# elektrosluch_mini_city.net
KiCad netlist of a schematic drawn in EAGLE
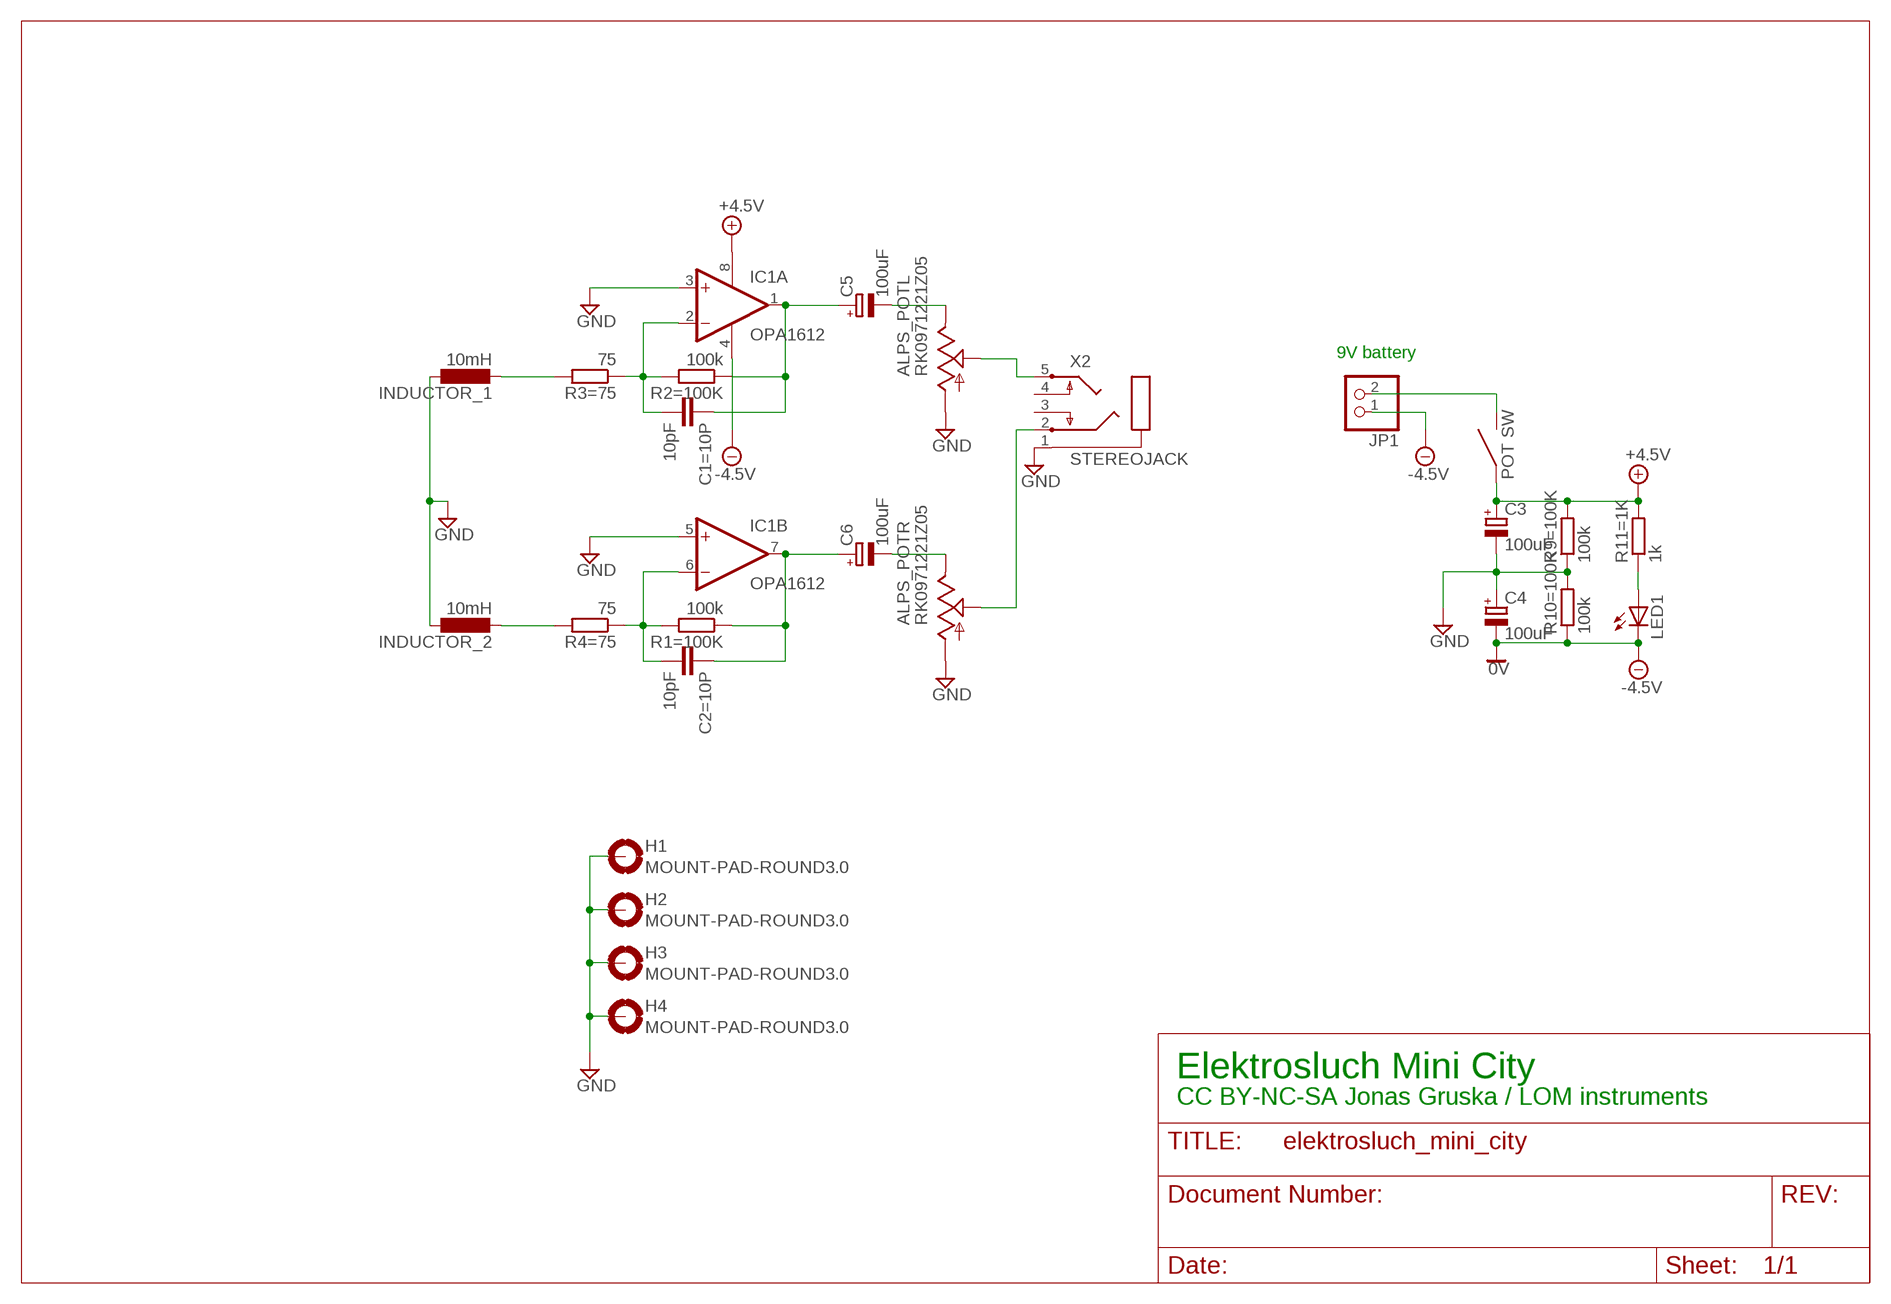
[diagram p0: schematic, sheet 1]

(export (version "E")
  (design (tool "Eeschema 10.0.6"))
  (components
    (comp (ref "ALPS_POT")
      (value "RK0971221Z05")
      (footprint "eagle-import:ALPS_RK0971221Z0X")
      (libsource (lib "eagle-import") (part "ALPS_RK0971221Z0N"))
    )
    (comp (ref "C1=10P")
      (value "10pF")
      (footprint "eagle-import:C050-024X044")
      (libsource (lib "eagle-import") (part "C-EU050-024X044"))
    )
    (comp (ref "C2=10P")
      (value "10pF")
      (footprint "eagle-import:C050-024X044")
      (libsource (lib "eagle-import") (part "C-EU050-024X044"))
    )
    (comp (ref "C3")
      (value "100uF")
      (footprint "eagle-import:E2,5-6")
      (libsource (lib "eagle-import") (part "CPOL-EUE2.5-6"))
    )
    (comp (ref "C4")
      (value "100uF")
      (footprint "eagle-import:E2,5-6")
      (libsource (lib "eagle-import") (part "CPOL-EUE2.5-6"))
    )
    (comp (ref "C5")
      (value "100uF")
      (footprint "eagle-import:E2,5-6")
      (libsource (lib "eagle-import") (part "CPOL-EUE2.5-6"))
    )
    (comp (ref "C6")
      (value "100uF")
      (footprint "eagle-import:E2,5-6")
      (libsource (lib "eagle-import") (part "CPOL-EUE2.5-6"))
    )
    (comp (ref "H1")
      (value "MOUNT-PAD-ROUND3.0")
      (footprint "eagle-import:3,0-PAD")
      (libsource (lib "eagle-import") (part "MOUNT-PAD-ROUND3.0"))
    )
    (comp (ref "H2")
      (value "MOUNT-PAD-ROUND3.0")
      (footprint "eagle-import:3,0-PAD")
      (libsource (lib "eagle-import") (part "MOUNT-PAD-ROUND3.0"))
    )
    (comp (ref "H3")
      (value "MOUNT-PAD-ROUND3.0")
      (footprint "eagle-import:3,0-PAD")
      (libsource (lib "eagle-import") (part "MOUNT-PAD-ROUND3.0"))
    )
    (comp (ref "H4")
      (value "MOUNT-PAD-ROUND3.0")
      (footprint "eagle-import:3,0-PAD")
      (libsource (lib "eagle-import") (part "MOUNT-PAD-ROUND3.0"))
    )
    (comp (ref "IC1")
      (value "OPA1612")
      (footprint "eagle-import:SO08")
      (libsource (lib "eagle-import") (part "OPA2UA134"))
    )
    (comp (ref "INDUCTOR_1")
      (value "10mH")
      (footprint "eagle-import:COIL")
      (libsource (lib "eagle-import") (part "COIL"))
    )
    (comp (ref "INDUCTOR_2")
      (value "10mH")
      (footprint "eagle-import:COIL")
      (libsource (lib "eagle-import") (part "COIL"))
    )
    (comp (ref "JP1")
      (value "PINHD-1X2")
      (footprint "eagle-import:1X02")
      (libsource (lib "eagle-import") (part "PINHD-1X2"))
    )
    (comp (ref "LED1")
      (value "LED3MM")
      (footprint "eagle-import:LED3MM")
      (libsource (lib "eagle-import") (part "LED3MM"))
    )
    (comp (ref "R1=100K")
      (value "100k")
      (footprint "eagle-import:0204_7")
      (libsource (lib "eagle-import") (part "R-EU_0204/7"))
    )
    (comp (ref "R2=100K")
      (value "100k")
      (footprint "eagle-import:0204_7")
      (libsource (lib "eagle-import") (part "R-EU_0204/7"))
    )
    (comp (ref "R3=75")
      (value "75")
      (footprint "eagle-import:0204_7")
      (libsource (lib "eagle-import") (part "R-EU_0204/7"))
    )
    (comp (ref "R4=75")
      (value "75")
      (footprint "eagle-import:0204_7")
      (libsource (lib "eagle-import") (part "R-EU_0204/7"))
    )
    (comp (ref "R9=100K")
      (value "100k")
      (footprint "eagle-import:0204_7")
      (libsource (lib "eagle-import") (part "R-EU_0204/7"))
    )
    (comp (ref "R10=100K")
      (value "100k")
      (footprint "eagle-import:0204_7")
      (libsource (lib "eagle-import") (part "R-EU_0204/7"))
    )
    (comp (ref "R11=1K")
      (value "1k")
      (footprint "eagle-import:0204_7")
      (libsource (lib "eagle-import") (part "R-EU_0204/7"))
    )
    (comp (ref "X2")
      (value "STEREOJACK")
      (footprint "eagle-import:STX3100")
      (libsource (lib "eagle-import") (part "STEREOJACK"))
    )
  )
  (nets
    (net (code "1") (name "+4.5V") (class "Default")
      (node (ref "ALPS_POT") (pin "S1") (pinfunction "S1_S1") (pintype "power_in"))
      (node (ref "C3") (pin "+") (pinfunction "+_+") (pintype "passive"))
      (node (ref "IC1") (pin "8") (pinfunction "V+_8") (pintype "power_in"))
      (node (ref "R11=1K") (pin "2") (pinfunction "2_2") (pintype "passive"))
      (node (ref "R9=100K") (pin "2") (pinfunction "2_2") (pintype "passive"))
    )
    (net (code "2") (name "-4.5V") (class "Default")
      (node (ref "C4") (pin "-") (pinfunction "-_-") (pintype "passive"))
      (node (ref "IC1") (pin "4") (pinfunction "V-_4") (pintype "power_in"))
      (node (ref "JP1") (pin "1") (pinfunction "1_1") (pintype "passive"))
      (node (ref "LED1") (pin "K") (pinfunction "C_K") (pintype "passive"))
      (node (ref "R10=100K") (pin "1") (pinfunction "1_1") (pintype "passive"))
    )
    (net (code "3") (name "GND") (class "Default")
      (node (ref "ALPS_POT") (pin "G1") (pinfunction "1_G1") (pintype "passive"))
      (node (ref "ALPS_POT") (pin "G2") (pinfunction "1_G2") (pintype "passive"))
      (node (ref "C3") (pin "-") (pinfunction "-_-") (pintype "passive"))
      (node (ref "C4") (pin "+") (pinfunction "+_+") (pintype "passive"))
      (node (ref "H1") (pin "B3,0") (pinfunction "MOUNT_B3,0") (pintype "passive"))
      (node (ref "H2") (pin "B3,0") (pinfunction "MOUNT_B3,0") (pintype "passive"))
      (node (ref "H3") (pin "B3,0") (pinfunction "MOUNT_B3,0") (pintype "passive"))
      (node (ref "H4") (pin "B3,0") (pinfunction "MOUNT_B3,0") (pintype "passive"))
      (node (ref "IC1") (pin "3") (pinfunction "+IN_3") (pintype "input"))
      (node (ref "IC1") (pin "5") (pinfunction "+IN_5") (pintype "input"))
      (node (ref "INDUCTOR_1") (pin "P$1") (pinfunction "1_P$1") (pintype "passive"))
      (node (ref "INDUCTOR_2") (pin "P$1") (pinfunction "1_P$1") (pintype "passive"))
      (node (ref "R10=100K") (pin "2") (pinfunction "2_2") (pintype "passive"))
      (node (ref "R9=100K") (pin "1") (pinfunction "1_1") (pintype "passive"))
      (node (ref "X2") (pin "1") (pinfunction "1_1") (pintype "passive"))
    )
    (net (code "4") (name "Net-(ALPS_POT-PadS2)") (class "Default")
      (node (ref "ALPS_POT") (pin "S2") (pinfunction "S2_S2") (pintype "power_in"))
      (node (ref "JP1") (pin "2") (pinfunction "2_2") (pintype "passive"))
    )
    (net (code "5") (name "Net-(ALPS_POTB-2)") (class "Default")
      (node (ref "ALPS_POT") (pin "O1") (pinfunction "2_O1") (pintype "passive"))
      (node (ref "X2") (pin "5") (pinfunction "5_5") (pintype "passive"))
    )
    (net (code "6") (name "Net-(ALPS_POTB-3)") (class "Default")
      (node (ref "ALPS_POT") (pin "I1") (pinfunction "3_I1") (pintype "passive"))
      (node (ref "C5") (pin "-") (pinfunction "-_-") (pintype "passive"))
    )
    (net (code "7") (name "Net-(ALPS_POTC-2)") (class "Default")
      (node (ref "ALPS_POT") (pin "O2") (pinfunction "2_O2") (pintype "passive"))
      (node (ref "X2") (pin "2") (pinfunction "2_2") (pintype "passive"))
    )
    (net (code "8") (name "Net-(ALPS_POTC-3)") (class "Default")
      (node (ref "ALPS_POT") (pin "I2") (pinfunction "3_I2") (pintype "passive"))
      (node (ref "C6") (pin "-") (pinfunction "-_-") (pintype "passive"))
    )
    (net (code "9") (name "Net-(IC1A--IN)") (class "Default")
      (node (ref "C1=10P") (pin "2") (pinfunction "2_2") (pintype "passive"))
      (node (ref "IC1") (pin "2") (pinfunction "-IN_2") (pintype "input"))
      (node (ref "R2=100K") (pin "2") (pinfunction "2_2") (pintype "passive"))
      (node (ref "R3=75") (pin "1") (pinfunction "1_1") (pintype "passive"))
    )
    (net (code "10") (name "Net-(IC1A-OUT)") (class "Default")
      (node (ref "C1=10P") (pin "1") (pinfunction "1_1") (pintype "passive"))
      (node (ref "C5") (pin "+") (pinfunction "+_+") (pintype "passive"))
      (node (ref "IC1") (pin "1") (pinfunction "OUT_1") (pintype "output"))
      (node (ref "R2=100K") (pin "1") (pinfunction "1_1") (pintype "passive"))
    )
    (net (code "11") (name "Net-(IC1B--IN)") (class "Default")
      (node (ref "C2=10P") (pin "2") (pinfunction "2_2") (pintype "passive"))
      (node (ref "IC1") (pin "6") (pinfunction "-IN_6") (pintype "input"))
      (node (ref "R1=100K") (pin "2") (pinfunction "2_2") (pintype "passive"))
      (node (ref "R4=75") (pin "1") (pinfunction "1_1") (pintype "passive"))
    )
    (net (code "12") (name "Net-(IC1B-OUT)") (class "Default")
      (node (ref "C2=10P") (pin "1") (pinfunction "1_1") (pintype "passive"))
      (node (ref "C6") (pin "+") (pinfunction "+_+") (pintype "passive"))
      (node (ref "IC1") (pin "7") (pinfunction "OUT_7") (pintype "output"))
      (node (ref "R1=100K") (pin "1") (pinfunction "1_1") (pintype "passive"))
    )
    (net (code "13") (name "Net-(INDUCTOR_1-2)") (class "Default")
      (node (ref "INDUCTOR_1") (pin "P$2") (pinfunction "2_P$2") (pintype "passive"))
      (node (ref "R3=75") (pin "2") (pinfunction "2_2") (pintype "passive"))
    )
    (net (code "14") (name "Net-(INDUCTOR_2-2)") (class "Default")
      (node (ref "INDUCTOR_2") (pin "P$2") (pinfunction "2_P$2") (pintype "passive"))
      (node (ref "R4=75") (pin "2") (pinfunction "2_2") (pintype "passive"))
    )
    (net (code "15") (name "Net-(LED1-PadA)") (class "Default")
      (node (ref "LED1") (pin "A") (pinfunction "A_A") (pintype "passive"))
      (node (ref "R11=1K") (pin "1") (pinfunction "1_1") (pintype "passive"))
    )
    (net (code "16") (name "unconnected-(X2-Pad3)") (class "Default")
      (node (ref "X2") (pin "3") (pinfunction "3_3") (pintype "passive"))
    )
    (net (code "17") (name "unconnected-(X2-Pad4)") (class "Default")
      (node (ref "X2") (pin "4") (pinfunction "4_4") (pintype "passive"))
    )
  )
)
